# USB_Multiplicator_2023.net
KiCad netlist of a schematic drawn in EAGLE
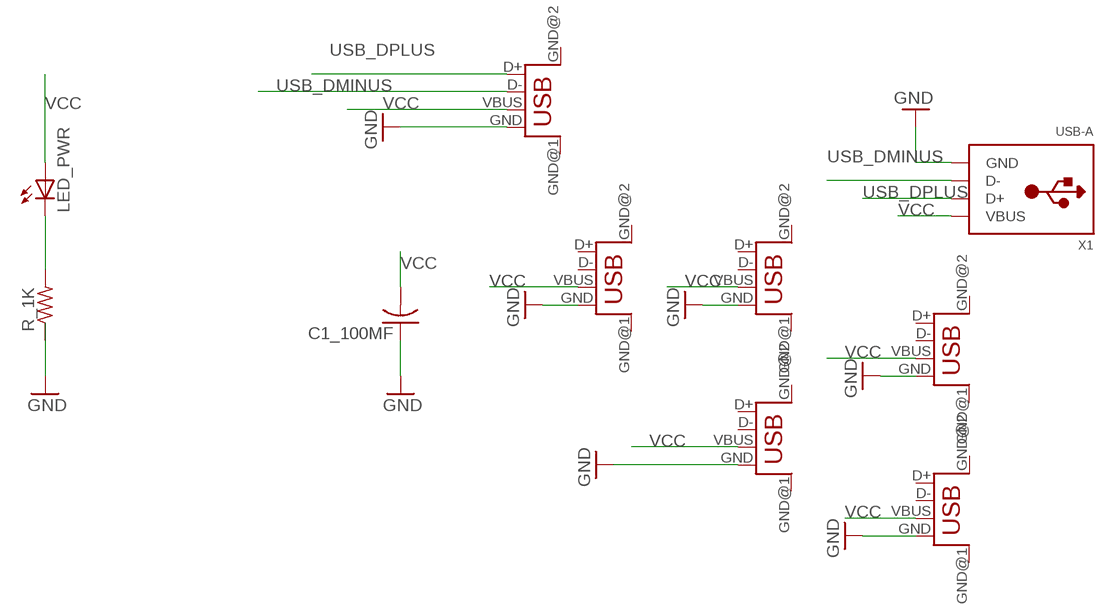
[diagram p0: schematic, sheet 1]

(export (version "E")
  (design (tool "Eeschema 10.0.6"))
  (components
    (comp (ref "C1_100MF")
      (value "C-US025-030X050")
      (footprint "eagle-import:C025-030X050")
      (libsource (lib "eagle-import") (part "C-US025-030X050"))
    )
    (comp (ref "LED_PWR")
      (value "LEDSMT1206")
      (footprint "eagle-import:1206")
      (libsource (lib "eagle-import") (part "LEDSMT1206"))
    )
    (comp (ref "R_1K")
      (value "R-US_R1206")
      (footprint "eagle-import:R1206")
      (libsource (lib "eagle-import") (part "R-US_R1206"))
    )
    (comp (ref "USB_OUT_2")
      (value "USB")
      (footprint "eagle-import:USB-FEMALE-A-PTH")
      (libsource (lib "eagle-import") (part "USB"))
    )
    (comp (ref "USB_OUT_3")
      (value "USB")
      (footprint "eagle-import:USB-FEMALE-A-PTH")
      (libsource (lib "eagle-import") (part "USB"))
    )
    (comp (ref "USB_OUT_4")
      (value "USB")
      (footprint "eagle-import:USB-FEMALE-A-PTH")
      (libsource (lib "eagle-import") (part "USB"))
    )
    (comp (ref "USB_OUT_5")
      (value "USB")
      (footprint "eagle-import:USB-FEMALE-A-PTH")
      (libsource (lib "eagle-import") (part "USB"))
    )
    (comp (ref "USB_OUT_6")
      (value "USB")
      (footprint "eagle-import:USB-FEMALE-A-PTH")
      (libsource (lib "eagle-import") (part "USB"))
    )
    (comp (ref "USB_OUT_WITH_DATA_1")
      (value "USB")
      (footprint "eagle-import:USB-FEMALE-A-PTH")
      (libsource (lib "eagle-import") (part "USB"))
    )
    (comp (ref "X1")
      (value "USB-A")
      (footprint "eagle-import:MOLEX_480371000")
      (libsource (lib "eagle-import") (part "USB-A"))
    )
  )
  (nets
    (net (code "1") (name "/USB_DMINUS") (class "Default")
      (node (ref "USB_OUT_WITH_DATA_1") (pin "D-") (pinfunction "D-_D-") (pintype "bidirectional"))
      (node (ref "X1") (pin "2") (pinfunction "D-_2") (pintype "bidirectional"))
    )
    (net (code "2") (name "/USB_DPLUS") (class "Default")
      (node (ref "USB_OUT_WITH_DATA_1") (pin "D+") (pinfunction "D+_D+") (pintype "bidirectional"))
      (node (ref "X1") (pin "3") (pinfunction "D+_3") (pintype "bidirectional"))
    )
    (net (code "3") (name "/VCC") (class "Default")
      (node (ref "C1_100MF") (pin "2") (pinfunction "2_2") (pintype "passive"))
      (node (ref "LED_PWR") (pin "A") (pinfunction "A_A") (pintype "passive"))
      (node (ref "USB_OUT_2") (pin "VBUS") (pinfunction "VBUS_VBUS") (pintype "bidirectional"))
      (node (ref "USB_OUT_3") (pin "VBUS") (pinfunction "VBUS_VBUS") (pintype "bidirectional"))
      (node (ref "USB_OUT_4") (pin "VBUS") (pinfunction "VBUS_VBUS") (pintype "bidirectional"))
      (node (ref "USB_OUT_5") (pin "VBUS") (pinfunction "VBUS_VBUS") (pintype "bidirectional"))
      (node (ref "USB_OUT_6") (pin "VBUS") (pinfunction "VBUS_VBUS") (pintype "bidirectional"))
      (node (ref "USB_OUT_WITH_DATA_1") (pin "VBUS") (pinfunction "VBUS_VBUS") (pintype "bidirectional"))
      (node (ref "X1") (pin "1") (pinfunction "VBUS_1") (pintype "power_in"))
    )
    (net (code "4") (name "GND") (class "Default")
      (node (ref "C1_100MF") (pin "1") (pinfunction "1_1") (pintype "passive"))
      (node (ref "R_1K") (pin "1") (pinfunction "1_1") (pintype "passive"))
      (node (ref "USB_OUT_2") (pin "GND") (pinfunction "GND_GND") (pintype "bidirectional"))
      (node (ref "USB_OUT_3") (pin "GND") (pinfunction "GND_GND") (pintype "bidirectional"))
      (node (ref "USB_OUT_4") (pin "GND") (pinfunction "GND_GND") (pintype "bidirectional"))
      (node (ref "USB_OUT_5") (pin "GND") (pinfunction "GND_GND") (pintype "bidirectional"))
      (node (ref "USB_OUT_6") (pin "GND") (pinfunction "GND_GND") (pintype "bidirectional"))
      (node (ref "USB_OUT_WITH_DATA_1") (pin "GND") (pinfunction "GND_GND") (pintype "bidirectional"))
      (node (ref "X1") (pin "4") (pinfunction "GND_4") (pintype "power_in"))
    )
    (net (code "5") (name "Net-(LED_PWR-PadC)") (class "Default")
      (node (ref "LED_PWR") (pin "C") (pinfunction "C_C") (pintype "passive"))
      (node (ref "R_1K") (pin "2") (pinfunction "2_2") (pintype "passive"))
    )
    (net (code "6") (name "unconnected-(USB_OUT_2-GND-PadGND@1)") (class "Default")
      (node (ref "USB_OUT_2") (pin "GND@1") (pinfunction "GND_GND@1") (pintype "bidirectional"))
    )
    (net (code "7") (name "unconnected-(USB_OUT_2-GND-PadGND@2)") (class "Default")
      (node (ref "USB_OUT_2") (pin "GND@2") (pinfunction "GND_GND@2") (pintype "bidirectional"))
    )
    (net (code "8") (name "unconnected-(USB_OUT_2-PadD+)") (class "Default")
      (node (ref "USB_OUT_2") (pin "D+") (pinfunction "D+_D+") (pintype "bidirectional"))
    )
    (net (code "9") (name "unconnected-(USB_OUT_2-PadD-)") (class "Default")
      (node (ref "USB_OUT_2") (pin "D-") (pinfunction "D-_D-") (pintype "bidirectional"))
    )
    (net (code "10") (name "unconnected-(USB_OUT_3-GND-PadGND@1)") (class "Default")
      (node (ref "USB_OUT_3") (pin "GND@1") (pinfunction "GND_GND@1") (pintype "bidirectional"))
    )
    (net (code "11") (name "unconnected-(USB_OUT_3-GND-PadGND@2)") (class "Default")
      (node (ref "USB_OUT_3") (pin "GND@2") (pinfunction "GND_GND@2") (pintype "bidirectional"))
    )
    (net (code "12") (name "unconnected-(USB_OUT_3-PadD+)") (class "Default")
      (node (ref "USB_OUT_3") (pin "D+") (pinfunction "D+_D+") (pintype "bidirectional"))
    )
    (net (code "13") (name "unconnected-(USB_OUT_3-PadD-)") (class "Default")
      (node (ref "USB_OUT_3") (pin "D-") (pinfunction "D-_D-") (pintype "bidirectional"))
    )
    (net (code "14") (name "unconnected-(USB_OUT_4-GND-PadGND@1)") (class "Default")
      (node (ref "USB_OUT_4") (pin "GND@1") (pinfunction "GND_GND@1") (pintype "bidirectional"))
    )
    (net (code "15") (name "unconnected-(USB_OUT_4-GND-PadGND@2)") (class "Default")
      (node (ref "USB_OUT_4") (pin "GND@2") (pinfunction "GND_GND@2") (pintype "bidirectional"))
    )
    (net (code "16") (name "unconnected-(USB_OUT_4-PadD+)") (class "Default")
      (node (ref "USB_OUT_4") (pin "D+") (pinfunction "D+_D+") (pintype "bidirectional"))
    )
    (net (code "17") (name "unconnected-(USB_OUT_4-PadD-)") (class "Default")
      (node (ref "USB_OUT_4") (pin "D-") (pinfunction "D-_D-") (pintype "bidirectional"))
    )
    (net (code "18") (name "unconnected-(USB_OUT_5-GND-PadGND@1)") (class "Default")
      (node (ref "USB_OUT_5") (pin "GND@1") (pinfunction "GND_GND@1") (pintype "bidirectional"))
    )
    (net (code "19") (name "unconnected-(USB_OUT_5-GND-PadGND@2)") (class "Default")
      (node (ref "USB_OUT_5") (pin "GND@2") (pinfunction "GND_GND@2") (pintype "bidirectional"))
    )
    (net (code "20") (name "unconnected-(USB_OUT_5-PadD+)") (class "Default")
      (node (ref "USB_OUT_5") (pin "D+") (pinfunction "D+_D+") (pintype "bidirectional"))
    )
    (net (code "21") (name "unconnected-(USB_OUT_5-PadD-)") (class "Default")
      (node (ref "USB_OUT_5") (pin "D-") (pinfunction "D-_D-") (pintype "bidirectional"))
    )
    (net (code "22") (name "unconnected-(USB_OUT_6-GND-PadGND@1)") (class "Default")
      (node (ref "USB_OUT_6") (pin "GND@1") (pinfunction "GND_GND@1") (pintype "bidirectional"))
    )
    (net (code "23") (name "unconnected-(USB_OUT_6-GND-PadGND@2)") (class "Default")
      (node (ref "USB_OUT_6") (pin "GND@2") (pinfunction "GND_GND@2") (pintype "bidirectional"))
    )
    (net (code "24") (name "unconnected-(USB_OUT_6-PadD+)") (class "Default")
      (node (ref "USB_OUT_6") (pin "D+") (pinfunction "D+_D+") (pintype "bidirectional"))
    )
    (net (code "25") (name "unconnected-(USB_OUT_6-PadD-)") (class "Default")
      (node (ref "USB_OUT_6") (pin "D-") (pinfunction "D-_D-") (pintype "bidirectional"))
    )
    (net (code "26") (name "unconnected-(USB_OUT_WITH_DATA_1-GND-PadGND@1)") (class "Default")
      (node (ref "USB_OUT_WITH_DATA_1") (pin "GND@1") (pinfunction "GND_GND@1") (pintype "bidirectional"))
    )
    (net (code "27") (name "unconnected-(USB_OUT_WITH_DATA_1-GND-PadGND@2)") (class "Default")
      (node (ref "USB_OUT_WITH_DATA_1") (pin "GND@2") (pinfunction "GND_GND@2") (pintype "bidirectional"))
    )
  )
)
